# illuminator_base.net
KiCad netlist of a schematic drawn in EAGLE
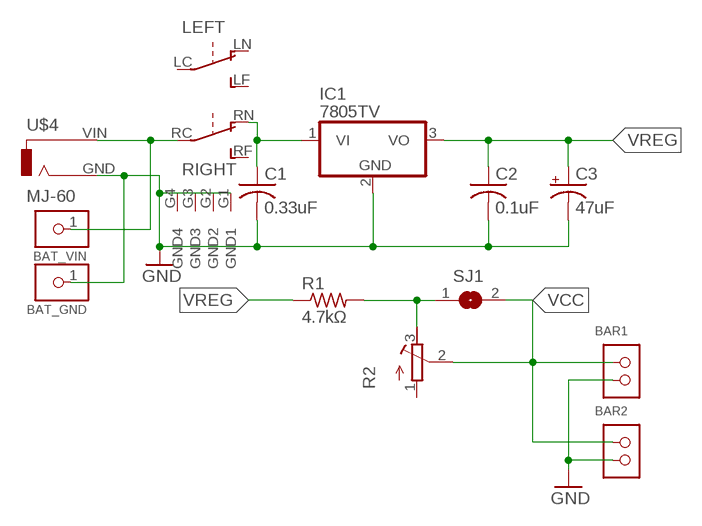
[diagram p0: schematic, sheet 1]

(export (version "E")
  (design (tool "Eeschema 10.0.6"))
  (components
    (comp (ref "BAR1")
      (value "1X020.8L")
      (footprint "eagle-import:1X02_0.8_UNSIGNED_LONG")
      (libsource (lib "eagle-import") (part "1X020.8L"))
    )
    (comp (ref "BAR2")
      (value "1X020.8L")
      (footprint "eagle-import:1X02_0.8_UNSIGNED_LONG")
      (libsource (lib "eagle-import") (part "1X020.8L"))
    )
    (comp (ref "BAT_GND")
      (value "1X0108L")
      (footprint "eagle-import:1X01_0.8_UNSIGNED_LONG")
      (libsource (lib "eagle-import") (part "1X0108L"))
    )
    (comp (ref "BAT_VIN")
      (value "1X0108L")
      (footprint "eagle-import:1X01_0.8_UNSIGNED_LONG")
      (libsource (lib "eagle-import") (part "1X0108L"))
    )
    (comp (ref "C1")
      (value "0.33uF")
      (footprint "eagle-import:C025-030X050")
      (libsource (lib "eagle-import") (part "C-US025-030X050"))
    )
    (comp (ref "C2")
      (value "0.1uF")
      (footprint "eagle-import:C025-030X050")
      (libsource (lib "eagle-import") (part "C-US025-030X050"))
    )
    (comp (ref "C3")
      (value "47uF")
      (footprint "eagle-import:E2-5")
      (libsource (lib "eagle-import") (part "CPOL-USE2-5"))
    )
    (comp (ref "IC1")
      (value "7805TV")
      (footprint "eagle-import:TO220V")
      (libsource (lib "eagle-import") (part "78TV05"))
    )
    (comp (ref "R1")
      (value "4.7kΩ")
      (footprint "eagle-import:0204_7")
      (libsource (lib "eagle-import") (part "R-US_0204/7"))
    )
    (comp (ref "R2")
      (value "R-TRIMM3339P")
      (footprint "eagle-import:RTRIM3339P")
      (libsource (lib "eagle-import") (part "R-TRIMM3339P"))
    )
    (comp (ref "SJ1") (value "SJ") (footprint "eagle-import:SJ") (libsource (lib "eagle-import") (part "SJ")))
    (comp (ref "U$3")
      (value "M-2022NB")
      (footprint "eagle-import:M-2022NB")
      (libsource (lib "eagle-import") (part "M-2022NB"))
    )
    (comp (ref "U$4")
      (value "MJ-60")
      (footprint "eagle-import:MJ-60")
      (libsource (lib "eagle-import") (part "MJ-60"))
    )
  )
  (nets
    (net (code "1") (name "GND") (class "Default")
      (node (ref "BAR1") (pin "2") (pinfunction "2_2") (pintype "passive"))
      (node (ref "BAR2") (pin "2") (pinfunction "2_2") (pintype "passive"))
      (node (ref "BAT_GND") (pin "1") (pinfunction "1_1") (pintype "passive"))
      (node (ref "C1") (pin "2") (pinfunction "2_2") (pintype "passive"))
      (node (ref "C2") (pin "2") (pinfunction "2_2") (pintype "passive"))
      (node (ref "C3") (pin "-") (pinfunction "-_-") (pintype "passive"))
      (node (ref "IC1") (pin "2") (pinfunction "GND_2") (pintype "passive"))
      (node (ref "U$3") (pin "G1") (pinfunction "GND1_G1") (pintype "passive"))
      (node (ref "U$3") (pin "G2") (pinfunction "GND2_G2") (pintype "passive"))
      (node (ref "U$3") (pin "G3") (pinfunction "GND3_G3") (pintype "passive"))
      (node (ref "U$3") (pin "G4") (pinfunction "GND4_G4") (pintype "passive"))
      (node (ref "U$4") (pin "GND") (pinfunction "GND_GND") (pintype "passive"))
    )
    (net (code "2") (name "Net-(IC1-VI)") (class "Default")
      (node (ref "C1") (pin "1") (pinfunction "1_1") (pintype "passive"))
      (node (ref "IC1") (pin "1") (pinfunction "VI_1") (pintype "input"))
      (node (ref "U$3") (pin "RN") (pinfunction "RIGHT_ON_RN") (pintype "passive"))
    )
    (net (code "3") (name "Net-(R2-A)") (class "Default")
      (node (ref "R1") (pin "2") (pinfunction "2_2") (pintype "passive"))
      (node (ref "R2") (pin "3") (pinfunction "A_3") (pintype "passive"))
      (node (ref "SJ1") (pin "1") (pinfunction "1_1") (pintype "passive"))
    )
    (net (code "4") (name "Net-(U$3-RIGHT_CENTER)") (class "Default")
      (node (ref "BAT_VIN") (pin "1") (pinfunction "1_1") (pintype "passive"))
      (node (ref "U$3") (pin "RC") (pinfunction "RIGHT_CENTER_RC") (pintype "passive"))
      (node (ref "U$4") (pin "VIN") (pinfunction "VIN_VIN") (pintype "passive"))
    )
    (net (code "5") (name "VCC") (class "Default")
      (node (ref "BAR1") (pin "1") (pinfunction "1_1") (pintype "passive"))
      (node (ref "BAR2") (pin "1") (pinfunction "1_1") (pintype "passive"))
      (node (ref "R2") (pin "2") (pinfunction "S_2") (pintype "passive"))
      (node (ref "SJ1") (pin "2") (pinfunction "2_2") (pintype "passive"))
    )
    (net (code "6") (name "VREG") (class "Default")
      (node (ref "C2") (pin "1") (pinfunction "1_1") (pintype "passive"))
      (node (ref "C3") (pin "+") (pinfunction "+_+") (pintype "passive"))
      (node (ref "IC1") (pin "3") (pinfunction "VO_3") (pintype "passive"))
      (node (ref "R1") (pin "1") (pinfunction "1_1") (pintype "passive"))
    )
    (net (code "7") (name "unconnected-(R2-E-Pad1)") (class "Default")
      (node (ref "R2") (pin "1") (pinfunction "E_1") (pintype "passive"))
    )
    (net (code "8") (name "unconnected-(U$3-LEFT_CENTER-PadLC)") (class "Default")
      (node (ref "U$3") (pin "LC") (pinfunction "LEFT_CENTER_LC") (pintype "passive"))
    )
    (net (code "9") (name "unconnected-(U$3-LEFT_OFF-PadLF)") (class "Default")
      (node (ref "U$3") (pin "LF") (pinfunction "LEFT_OFF_LF") (pintype "passive"))
    )
    (net (code "10") (name "unconnected-(U$3-LEFT_ON-PadLN)") (class "Default")
      (node (ref "U$3") (pin "LN") (pinfunction "LEFT_ON_LN") (pintype "passive"))
    )
    (net (code "11") (name "unconnected-(U$3-RIGHT_OFF-PadRF)") (class "Default")
      (node (ref "U$3") (pin "RF") (pinfunction "RIGHT_OFF_RF") (pintype "passive"))
    )
  )
)
